# BCTester.net
KiCad netlist of a schematic drawn in Altium Designer
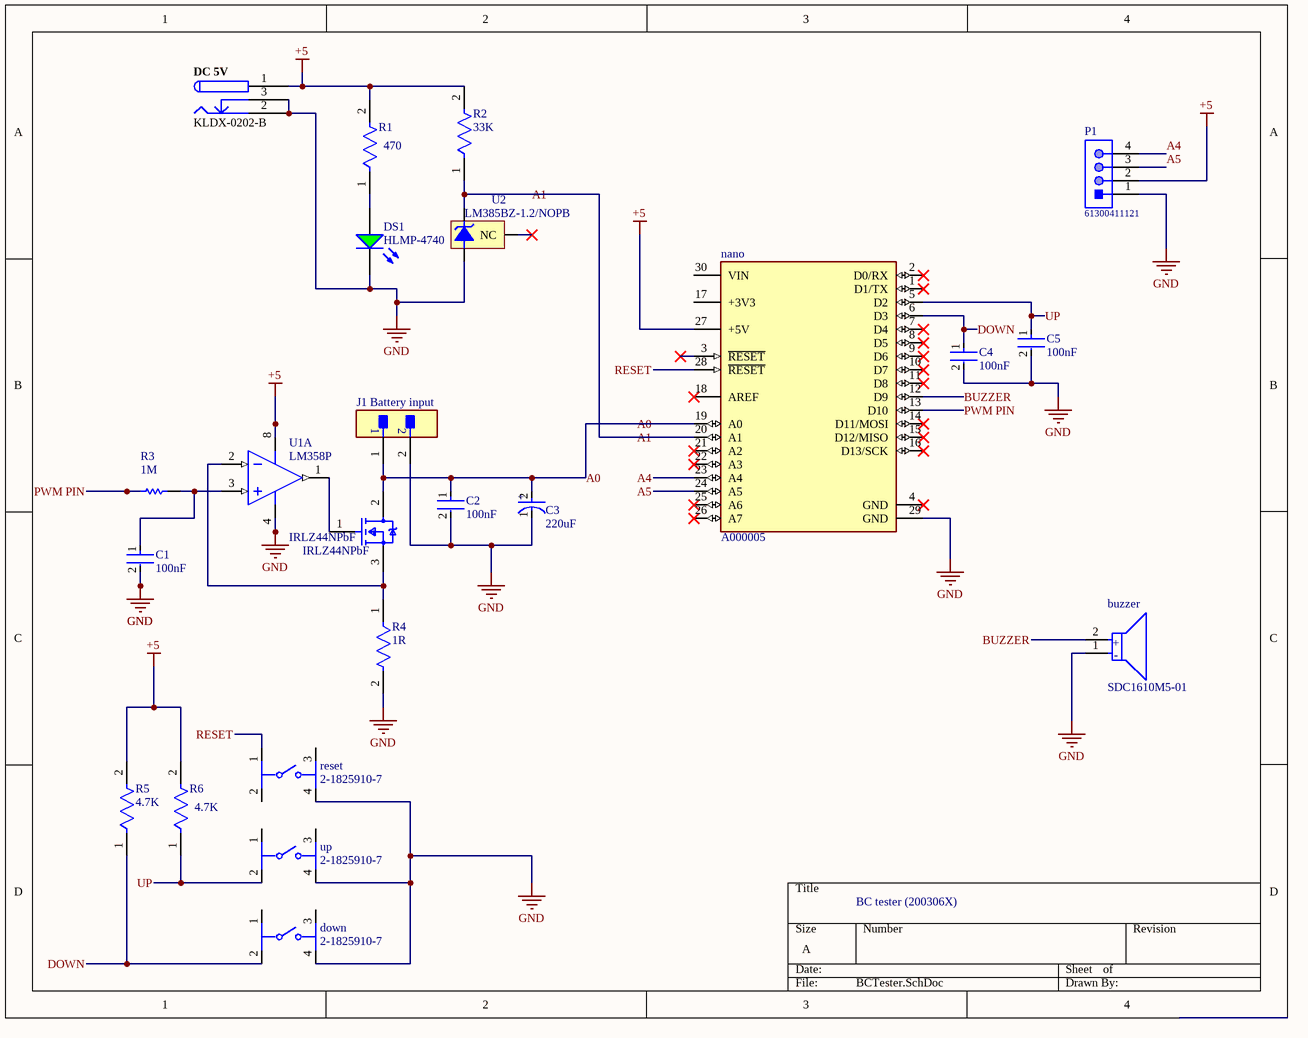
[diagram p0: BCTester.SchDoc]

(export (version "E")
  (design (tool "Eeschema 10.0.6"))
  (components
    (comp (ref "buzzer")
      (value "SDC1610M5-01")
      (footprint "FP-SDC1610M5-01-MFG")
      (description "AUDIO MAGNETIC INDICATOR 4-8V TH")
      (libsource (lib "Altium Content Vault") (part "f7ec632b6fea80cbef86dc3340f200c"))
    )
    (comp (ref "C1")
      (value "100nF")
      (footprint "FP-DE6_D7_T7_F7_5_d0_6-0-MFG")
      (description "CAP CER 1000PF 300VAC RADIAL")
      (fields (field (name "TOLERANCE") "20%"))
      (libsource (lib "Altium Content Vault") (part "7bc8f122f62ff4f5a687363419e79e3"))
    )
    (comp (ref "C2")
      (value "100nF")
      (footprint "FP-DE6_D7_T7_F7_5_d0_6-0-MFG")
      (description "CAP CER 1000PF 300VAC RADIAL")
      (fields (field (name "TOLERANCE") "20%"))
      (libsource (lib "Altium Content Vault") (part "7bc8f122f62ff4f5a687363419e79e3"))
    )
    (comp (ref "C3")
      (value "220uF")
      (footprint "FP-RAD-TH-D_8_0_5-L_11_5-MFG")
      (description "Aluminum Electrolytic Capacitors (Radial Lead Type) AEC-Q200 Qualified 220uF ±20% 25V")
      (fields (field (name "VOLTAGE") "25V") (field (name "TOLERANCE") "20%"))
      (libsource (lib "Altium Content Vault") (part "a00bbbee19879c290e62620ae7e47b1"))
    )
    (comp (ref "C4")
      (value "100nF")
      (footprint "FP-DE6_D7_T7_F7_5_d0_6-0-MFG")
      (description "CAP CER 1000PF 300VAC RADIAL")
      (fields (field (name "TOLERANCE") "20%"))
      (libsource (lib "Altium Content Vault") (part "7bc8f122f62ff4f5a687363419e79e3"))
    )
    (comp (ref "C5")
      (value "100nF")
      (footprint "FP-DE6_D7_T7_F7_5_d0_6-0-MFG")
      (description "CAP CER 1000PF 300VAC RADIAL")
      (fields (field (name "TOLERANCE") "20%"))
      (libsource (lib "Altium Content Vault") (part "7bc8f122f62ff4f5a687363419e79e3"))
    )
    (comp (ref "DC 5V")
      (value "KLDX-0202-B")
      (footprint "KYCN-KLDX-0202-B_V")
      (description "3 Conductor Power Jack, 2 break 2 aux contacts")
      (libsource (lib "Altium Content Vault") (part "KYCN-KLDX-0202-B-3"))
    )
    (comp (ref "down")
      (value "2-1825910-7")
      (footprint "FP-2-1825910-7-MFG")
      (description "SWITCH TACTILE SPST-NO 0.05A 24V")
      (fields
        (field (name "MANUFACTURER") "TE Connectivity")
        (field (name "OCTOPART") "https://octopart.com/2-1825910-7-te+connectivity-42270510")
      )
      (libsource (lib "Altium Content Vault") (part "b8895f3f4cefb76e1819d2863dba89b"))
    )
    (comp (ref "DS1")
      (value "HLMP-4740")
      (footprint "AVAG-HLMP-4740")
      (description "T-1 3/4 (5 mm) Low Current LED Lamp, Green, 1.9 V, -20 to 100 degC, 2-Pin THD, RoHS, Bulk")
      (fields (field (name "MANUFACTURER") "AvagoTechnologies"))
      (libsource (lib "Altium Content Vault") (part "LED-GREEN-AK-2"))
    )
    (comp (ref "IRLZ44NPbF")
      (value "IRLZ44NPbF")
      (footprint "FP-PG-TO220-3-MFG")
      (description "MOSFET N-CH 55V 47A TO220AB")
      (libsource (lib "Altium Content Vault") (part "b09f7f152735e370c1ea22a33fa83d6"))
    )
    (comp (ref "J1")
      (value "Battery input")
      (footprint "FP-M20-9990246-MFG")
      (description "CONN HEADER VERT 2POS 2.54MM")
      (fields
        (field (name "OCTOPART") "https://octopart.com/m20-9990246-harwin-2590635")
        (field (name "MANUFACTURER") "Harwin")
      )
      (libsource (lib "Altium Content Vault") (part "3bc925449376181038e59eaffc5286c"))
    )
    (comp (ref "nano")
      (value "A000005")
      (footprint "FP-A000005-MFG")
      (description "ARDUINO NANO ATMEGA328 EVAL BRD")
      (libsource (lib "Altium Content Vault") (part "d190c066e99afd1c6882cf92e11b2cc"))
    )
    (comp (ref "P1")
      (value "61300411121")
      (footprint "61300411121")
      (description "THT Vertical Pin Header WR-PHD, Pitch 2.54 mm, Single Row, 4 pins")
      (fields (field (name "MANUFACTURER") "Wurth Elektronik") (field (name "PUBLISHER") "WurthElektronik"))
      (libsource (lib "Altium Content Vault") (part "WE-CN-1P-M-R4"))
    )
    (comp (ref "R1")
      (value "470")
      (footprint "FP-RNC55-MFG")
      (description "RES 10K OHM 1/8W 1% AXIAL")
      (fields (field (name "TOLERANCE") "1%") (field (name "MANUFACTURER PART NUMBER") "RNC55H1002FSB14"))
      (libsource (lib "Altium Content Vault") (part "1029c3af85768c4190bb7ad29bc67b5"))
    )
    (comp (ref "R2")
      (value "33K")
      (footprint "FP-H8511KBYA-MFG")
      (description "RES 511K OHM 0.1% 1/4W AXIAL")
      (fields (field (name "TOLERANCE") "0.1%"))
      (libsource (lib "Altium Content Vault") (part "1029c3af85768c4190bb7ad29bc67b5"))
    )
    (comp (ref "R3")
      (value "1M")
      (footprint "RESA60-630X240")
      (description "Axial Resistor, 1 MOhm, +/- 1%, 250 mW, -55 to 155 degC, 2-Pin THD, RoHS, Bulk")
      (fields (field (name "TOLERANCE") "1%"))
      (libsource (lib "Altium Content Vault") (part "RES-2"))
    )
    (comp (ref "R4")
      (value "1R")
      (footprint "FP-PR01-MFG")
      (description "RES 75K OHM 1W 5% AXIAL")
      (fields (field (name "TOLERANCE") "5%"))
      (libsource (lib "Altium Content Vault") (part "1029c3af85768c4190bb7ad29bc67b5"))
    )
    (comp (ref "R5")
      (value "4.7K")
      (footprint "FP-MRS25-MFG")
      (description "RES 1K OHM 0.6W 1% AXIAL")
      (fields (field (name "TOLERANCE") "1%"))
      (libsource (lib "Altium Content Vault") (part "1029c3af85768c4190bb7ad29bc67b5"))
    )
    (comp (ref "R6")
      (value "4.7K")
      (footprint "FP-MRS25-MFG")
      (description "RES 1K OHM 0.6W 1% AXIAL")
      (fields (field (name "TOLERANCE") "1%"))
      (libsource (lib "Altium Content Vault") (part "1029c3af85768c4190bb7ad29bc67b5"))
    )
    (comp (ref "reset")
      (value "2-1825910-7")
      (footprint "FP-2-1825910-7-MFG")
      (description "SWITCH TACTILE SPST-NO 0.05A 24V")
      (fields
        (field (name "MANUFACTURER") "TE Connectivity")
        (field (name "OCTOPART") "https://octopart.com/2-1825910-7-te+connectivity-42270510")
      )
      (libsource (lib "Altium Content Vault") (part "b8895f3f4cefb76e1819d2863dba89b"))
    )
    (comp (ref "U1")
      (value "LM358P")
      (footprint "P0008A")
      (description "Dual Operational Amplifier, 3 to 32 V, 0 to 70 degC, 8-Pin PDIP (P), RoHS, Tape and Reel")
      (fields (field (name "MANUFACTURER") "Technik Industrial"))
      (libsource (lib "Altium Content Vault") (part "TI-LM_LPXXX-SO_DIP8"))
    )
    (comp (ref "U2")
      (value "LM385BZ-1.2/NOPB")
      (footprint "Z03A")
      (description "Micropower Voltage Reference Diode, 3-pin TO-92, Pb-Free")
      (fields (field (name "MANUFACTURER") "National Semiconductor"))
      (libsource (lib "Altium Content Vault") (part "PM-REF-LM113-IL3A"))
    )
    (comp (ref "up")
      (value "2-1825910-7")
      (footprint "FP-2-1825910-7-MFG")
      (description "SWITCH TACTILE SPST-NO 0.05A 24V")
      (fields
        (field (name "MANUFACTURER") "TE Connectivity")
        (field (name "OCTOPART") "https://octopart.com/2-1825910-7-te+connectivity-42270510")
      )
      (libsource (lib "Altium Content Vault") (part "b8895f3f4cefb76e1819d2863dba89b"))
    )
  )
  (nets
    (net (code "1") (name "+5") (class "Default")
      (node (ref "DC 5V") (pin "1") (pintype "power_in"))
      (node (ref "P1") (pin "2") (pinfunction "2_2") (pintype "passive"))
      (node (ref "R1") (pin "2") (pinfunction "2_2") (pintype "passive"))
      (node (ref "R2") (pin "2") (pinfunction "2_2") (pintype "passive"))
      (node (ref "R5") (pin "2") (pinfunction "2_2") (pintype "passive"))
      (node (ref "R6") (pin "2") (pinfunction "2_2") (pintype "passive"))
      (node (ref "U1") (pin "8") (pinfunction "VCC_8") (pintype "power_in"))
      (node (ref "nano") (pin "27") (pinfunction "+5V_27") (pintype "power_in"))
    )
    (net (code "3") (name "/A0") (class "Default")
      (node (ref "C2") (pin "1") (pinfunction "1_1") (pintype "passive"))
      (node (ref "C3") (pin "2") (pinfunction "A_2") (pintype "passive"))
      (node (ref "IRLZ44NPbF") (pin "2") (pinfunction "D_2") (pintype "passive"))
      (node (ref "J1") (pin "1") (pinfunction "1_1") (pintype "passive"))
      (node (ref "nano") (pin "19") (pinfunction "A0_19") (pintype "bidirectional"))
    )
    (net (code "4") (name "/A1") (class "Default")
      (node (ref "R2") (pin "1") (pinfunction "1_1") (pintype "passive"))
      (node (ref "U2") (pin "2") (pinfunction "+V_2") (pintype "passive"))
      (node (ref "nano") (pin "20") (pinfunction "A1_20") (pintype "bidirectional"))
    )
    (net (code "5") (name "/A4") (class "Default")
      (node (ref "P1") (pin "4") (pinfunction "4_4") (pintype "passive"))
      (node (ref "nano") (pin "23") (pinfunction "A4_23") (pintype "bidirectional"))
    )
    (net (code "6") (name "/A5") (class "Default")
      (node (ref "P1") (pin "3") (pinfunction "3_3") (pintype "passive"))
      (node (ref "nano") (pin "24") (pinfunction "A5_24") (pintype "bidirectional"))
    )
    (net (code "7") (name "/BUZZER") (class "Default")
      (node (ref "buzzer") (pin "2") (pinfunction "A_2") (pintype "passive"))
      (node (ref "nano") (pin "12") (pinfunction "D9_12") (pintype "bidirectional"))
    )
    (net (code "8") (name "/DOWN") (class "Default")
      (node (ref "C4") (pin "1") (pinfunction "1_1") (pintype "passive"))
      (node (ref "R5") (pin "1") (pinfunction "1_1") (pintype "passive"))
      (node (ref "down") (pin "2") (pinfunction "2_2") (pintype "passive"))
      (node (ref "nano") (pin "6") (pinfunction "D3_6") (pintype "bidirectional"))
    )
    (net (code "9") (name "/PWM PIN") (class "Default")
      (node (ref "R3") (pin "1") (pinfunction "1_1") (pintype "passive"))
      (node (ref "nano") (pin "13") (pinfunction "D10_13") (pintype "bidirectional"))
    )
    (net (code "10") (name "/RESET") (class "Default")
      (node (ref "nano") (pin "28") (pinfunction "~{RESET}_28") (pintype "input"))
      (node (ref "reset") (pin "1") (pinfunction "1_1") (pintype "passive"))
    )
    (net (code "11") (name "/UP") (class "Default")
      (node (ref "C5") (pin "1") (pinfunction "1_1") (pintype "passive"))
      (node (ref "R6") (pin "1") (pinfunction "1_1") (pintype "passive"))
      (node (ref "nano") (pin "5") (pinfunction "D2_5") (pintype "bidirectional"))
      (node (ref "up") (pin "2") (pinfunction "2_2") (pintype "passive"))
    )
    (net (code "12") (name "GND") (class "Default")
      (node (ref "C1") (pin "2") (pinfunction "2_2") (pintype "passive"))
      (node (ref "C2") (pin "2") (pinfunction "2_2") (pintype "passive"))
      (node (ref "C3") (pin "1") (pinfunction "C_1") (pintype "passive"))
      (node (ref "C4") (pin "2") (pinfunction "2_2") (pintype "passive"))
      (node (ref "C5") (pin "2") (pinfunction "2_2") (pintype "passive"))
      (node (ref "DC 5V") (pin "2") (pintype "power_in"))
      (node (ref "DC 5V") (pin "3") (pintype "power_in"))
      (node (ref "DS1") (pin "2") (pinfunction "K_2") (pintype "passive"))
      (node (ref "J1") (pin "2") (pinfunction "2_2") (pintype "passive"))
      (node (ref "P1") (pin "1") (pinfunction "1_1") (pintype "passive"))
      (node (ref "R4") (pin "2") (pinfunction "2_2") (pintype "passive"))
      (node (ref "U1") (pin "4") (pinfunction "GND_4") (pintype "power_in"))
      (node (ref "U2") (pin "3") (pinfunction "-V_3") (pintype "passive"))
      (node (ref "buzzer") (pin "1") (pinfunction "C_1") (pintype "passive"))
      (node (ref "down") (pin "4") (pinfunction "4_4") (pintype "passive"))
      (node (ref "nano") (pin "29") (pinfunction "GND_29") (pintype "power_in"))
      (node (ref "reset") (pin "4") (pinfunction "4_4") (pintype "passive"))
      (node (ref "up") (pin "4") (pinfunction "4_4") (pintype "passive"))
    )
    (net (code "13") (name "Net-(DS1-A)") (class "Default")
      (node (ref "DS1") (pin "1") (pinfunction "A_1") (pintype "passive"))
      (node (ref "R1") (pin "1") (pinfunction "1_1") (pintype "passive"))
    )
    (net (code "14") (name "Net-(IRLZ44NPbF-G)") (class "Default")
      (node (ref "IRLZ44NPbF") (pin "1") (pinfunction "G_1") (pintype "passive"))
      (node (ref "U1") (pin "1") (pinfunction "1OUT_1") (pintype "output"))
    )
    (net (code "15") (name "Net-(IRLZ44NPbF-S)") (class "Default")
      (node (ref "IRLZ44NPbF") (pin "3") (pinfunction "S_3") (pintype "passive"))
      (node (ref "R4") (pin "1") (pinfunction "1_1") (pintype "passive"))
      (node (ref "U1") (pin "2") (pinfunction "1IN-_2") (pintype "input"))
    )
    (net (code "16") (name "Net-(U1A-1IN+)") (class "Default")
      (node (ref "C1") (pin "1") (pinfunction "1_1") (pintype "passive"))
      (node (ref "R3") (pin "2") (pinfunction "2_2") (pintype "passive"))
      (node (ref "U1") (pin "3") (pinfunction "1IN+_3") (pintype "input"))
    )
    (net (code "17") (name "unconnected-(U2-NC-Pad1)") (class "Default")
      (node (ref "U2") (pin "1") (pinfunction "NC_1") (pintype "passive+no_connect"))
    )
    (net (code "18") (name "unconnected-(down-Pad1)") (class "Default")
      (node (ref "down") (pin "1") (pinfunction "1_1") (pintype "passive"))
    )
    (net (code "19") (name "unconnected-(down-Pad3)") (class "Default")
      (node (ref "down") (pin "3") (pinfunction "3_3") (pintype "passive"))
    )
    (net (code "20") (name "unconnected-(nano-+3V3-Pad17)") (class "Default")
      (node (ref "nano") (pin "17") (pinfunction "+3V3_17") (pintype "power_in"))
    )
    (net (code "21") (name "unconnected-(nano-A2-Pad21)") (class "Default")
      (node (ref "nano") (pin "21") (pinfunction "A2_21") (pintype "bidirectional+no_connect"))
    )
    (net (code "22") (name "unconnected-(nano-A3-Pad22)") (class "Default")
      (node (ref "nano") (pin "22") (pinfunction "A3_22") (pintype "bidirectional+no_connect"))
    )
    (net (code "23") (name "unconnected-(nano-A6-Pad25)") (class "Default")
      (node (ref "nano") (pin "25") (pinfunction "A6_25") (pintype "bidirectional+no_connect"))
    )
    (net (code "24") (name "unconnected-(nano-A7-Pad26)") (class "Default")
      (node (ref "nano") (pin "26") (pinfunction "A7_26") (pintype "bidirectional+no_connect"))
    )
    (net (code "25") (name "unconnected-(nano-AREF-Pad18)") (class "Default")
      (node (ref "nano") (pin "18") (pinfunction "AREF_18") (pintype "passive+no_connect"))
    )
    (net (code "26") (name "unconnected-(nano-D0{slash}RX-Pad2)") (class "Default")
      (node (ref "nano") (pin "2") (pinfunction "D0/RX_2") (pintype "bidirectional+no_connect"))
    )
    (net (code "27") (name "unconnected-(nano-D1{slash}TX-Pad1)") (class "Default")
      (node (ref "nano") (pin "1") (pinfunction "D1/TX_1") (pintype "bidirectional+no_connect"))
    )
    (net (code "28") (name "unconnected-(nano-D4-Pad7)") (class "Default")
      (node (ref "nano") (pin "7") (pinfunction "D4_7") (pintype "bidirectional+no_connect"))
    )
    (net (code "29") (name "unconnected-(nano-D5-Pad8)") (class "Default")
      (node (ref "nano") (pin "8") (pinfunction "D5_8") (pintype "bidirectional+no_connect"))
    )
    (net (code "30") (name "unconnected-(nano-D6-Pad9)") (class "Default")
      (node (ref "nano") (pin "9") (pinfunction "D6_9") (pintype "bidirectional+no_connect"))
    )
    (net (code "31") (name "unconnected-(nano-D7-Pad10)") (class "Default")
      (node (ref "nano") (pin "10") (pinfunction "D7_10") (pintype "bidirectional+no_connect"))
    )
    (net (code "32") (name "unconnected-(nano-D8-Pad11)") (class "Default")
      (node (ref "nano") (pin "11") (pinfunction "D8_11") (pintype "bidirectional+no_connect"))
    )
    (net (code "33") (name "unconnected-(nano-D11{slash}MOSI-Pad14)") (class "Default")
      (node (ref "nano") (pin "14") (pinfunction "D11/MOSI_14") (pintype "bidirectional+no_connect"))
    )
    (net (code "34") (name "unconnected-(nano-D12{slash}MISO-Pad15)") (class "Default")
      (node (ref "nano") (pin "15") (pinfunction "D12/MISO_15") (pintype "bidirectional+no_connect"))
    )
    (net (code "35") (name "unconnected-(nano-D13{slash}SCK-Pad16)") (class "Default")
      (node (ref "nano") (pin "16") (pinfunction "D13/SCK_16") (pintype "bidirectional+no_connect"))
    )
    (net (code "36") (name "unconnected-(nano-GND-Pad4)") (class "Default")
      (node (ref "nano") (pin "4") (pinfunction "GND_4") (pintype "power_in+no_connect"))
    )
    (net (code "37") (name "unconnected-(nano-VIN-Pad30)") (class "Default")
      (node (ref "nano") (pin "30") (pinfunction "VIN_30") (pintype "power_in"))
    )
    (net (code "38") (name "unconnected-(nano-~{RESET}-Pad3)") (class "Default")
      (node (ref "nano") (pin "3") (pinfunction "~{RESET}_3") (pintype "input+no_connect"))
    )
    (net (code "39") (name "unconnected-(reset-Pad2)") (class "Default")
      (node (ref "reset") (pin "2") (pinfunction "2_2") (pintype "passive"))
    )
    (net (code "40") (name "unconnected-(reset-Pad3)") (class "Default")
      (node (ref "reset") (pin "3") (pinfunction "3_3") (pintype "passive"))
    )
    (net (code "41") (name "unconnected-(up-Pad1)") (class "Default")
      (node (ref "up") (pin "1") (pinfunction "1_1") (pintype "passive"))
    )
    (net (code "42") (name "unconnected-(up-Pad3)") (class "Default")
      (node (ref "up") (pin "3") (pinfunction "3_3") (pintype "passive"))
    )
  )
)
